# ExtraADC.net
KiCad netlist of a schematic drawn in Altium Designer
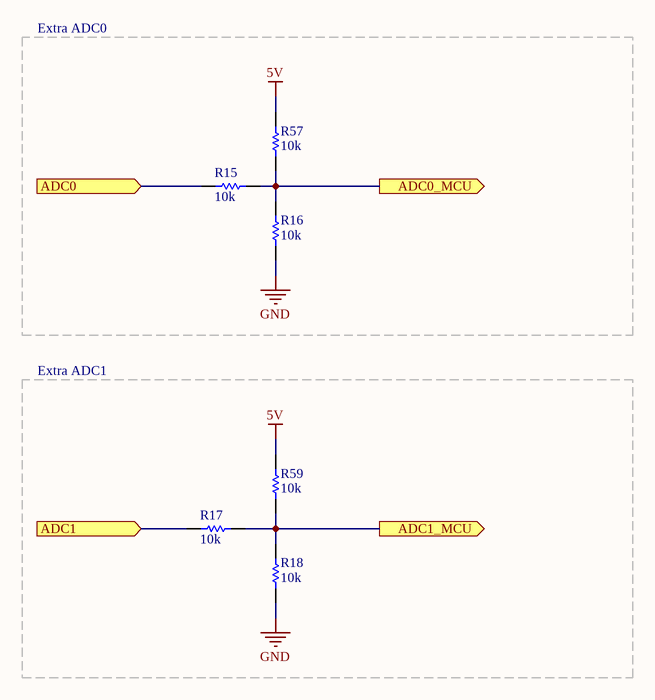
[diagram p0: ExtraADC.SchDoc]

(export (version "E")
  (design (tool "Eeschema 10.0.6"))
  (components
    (comp (ref "R15")
      (value "10k")
      (footprint "6-0805_M")
      (description "Resistor")
      (fields (field (name "PARTNUMBER") "RES.10k.1/8W.5%.SMD.0805") (field (name "MANUFACTURER") "Yageo"))
      (libsource (lib "IntLib") (part "Res"))
    )
    (comp (ref "R16")
      (value "10k")
      (footprint "6-0805_M")
      (description "Resistor")
      (fields (field (name "PARTNUMBER") "RES.10k.1/8W.5%.SMD.0805") (field (name "MANUFACTURER") "Yageo"))
      (libsource (lib "IntLib") (part "Res"))
    )
    (comp (ref "R17")
      (value "10k")
      (footprint "6-0805_M")
      (description "Resistor")
      (fields (field (name "PARTNUMBER") "RES.10k.1/8W.5%.SMD.0805") (field (name "MANUFACTURER") "Yageo"))
      (libsource (lib "IntLib") (part "Res"))
    )
    (comp (ref "R18")
      (value "10k")
      (footprint "6-0805_M")
      (description "Resistor")
      (fields (field (name "PARTNUMBER") "RES.10k.1/8W.5%.SMD.0805") (field (name "MANUFACTURER") "Yageo"))
      (libsource (lib "IntLib") (part "Res"))
    )
    (comp (ref "R57")
      (value "10k")
      (footprint "6-0805_M")
      (description "Resistor")
      (fields (field (name "PARTNUMBER") "RES.10k.1/8W.5%.SMD.0805") (field (name "MANUFACTURER") "Yageo"))
      (libsource (lib "IntLib") (part "Res"))
    )
    (comp (ref "R59")
      (value "10k")
      (footprint "6-0805_M")
      (description "Resistor")
      (fields (field (name "PARTNUMBER") "RES.10k.1/8W.5%.SMD.0805") (field (name "MANUFACTURER") "Yageo"))
      (libsource (lib "IntLib") (part "Res"))
    )
  )
  (nets
    (net (code "1") (name "/ADC0") (class "Default")
      (node (ref "R15") (pin "1") (pinfunction "1_1") (pintype "passive"))
    )
    (net (code "2") (name "/ADC0_MCU") (class "Default")
      (node (ref "R15") (pin "2") (pinfunction "2_2") (pintype "passive"))
      (node (ref "R16") (pin "2") (pinfunction "2_2") (pintype "passive"))
      (node (ref "R57") (pin "1") (pinfunction "1_1") (pintype "passive"))
    )
    (net (code "3") (name "/ADC1") (class "Default")
      (node (ref "R17") (pin "2") (pinfunction "2_2") (pintype "passive"))
    )
    (net (code "4") (name "/ADC1_MCU") (class "Default")
      (node (ref "R17") (pin "1") (pinfunction "1_1") (pintype "passive"))
      (node (ref "R18") (pin "2") (pinfunction "2_2") (pintype "passive"))
      (node (ref "R59") (pin "1") (pinfunction "1_1") (pintype "passive"))
    )
    (net (code "5") (name "5V") (class "Default")
      (node (ref "R57") (pin "2") (pinfunction "2_2") (pintype "passive"))
      (node (ref "R59") (pin "2") (pinfunction "2_2") (pintype "passive"))
    )
    (net (code "6") (name "GND") (class "Default")
      (node (ref "R16") (pin "1") (pinfunction "1_1") (pintype "passive"))
      (node (ref "R18") (pin "1") (pinfunction "1_1") (pintype "passive"))
    )
  )
)
